# Esquema_V3.net
KiCad netlist of a schematic drawn in Altium Designer
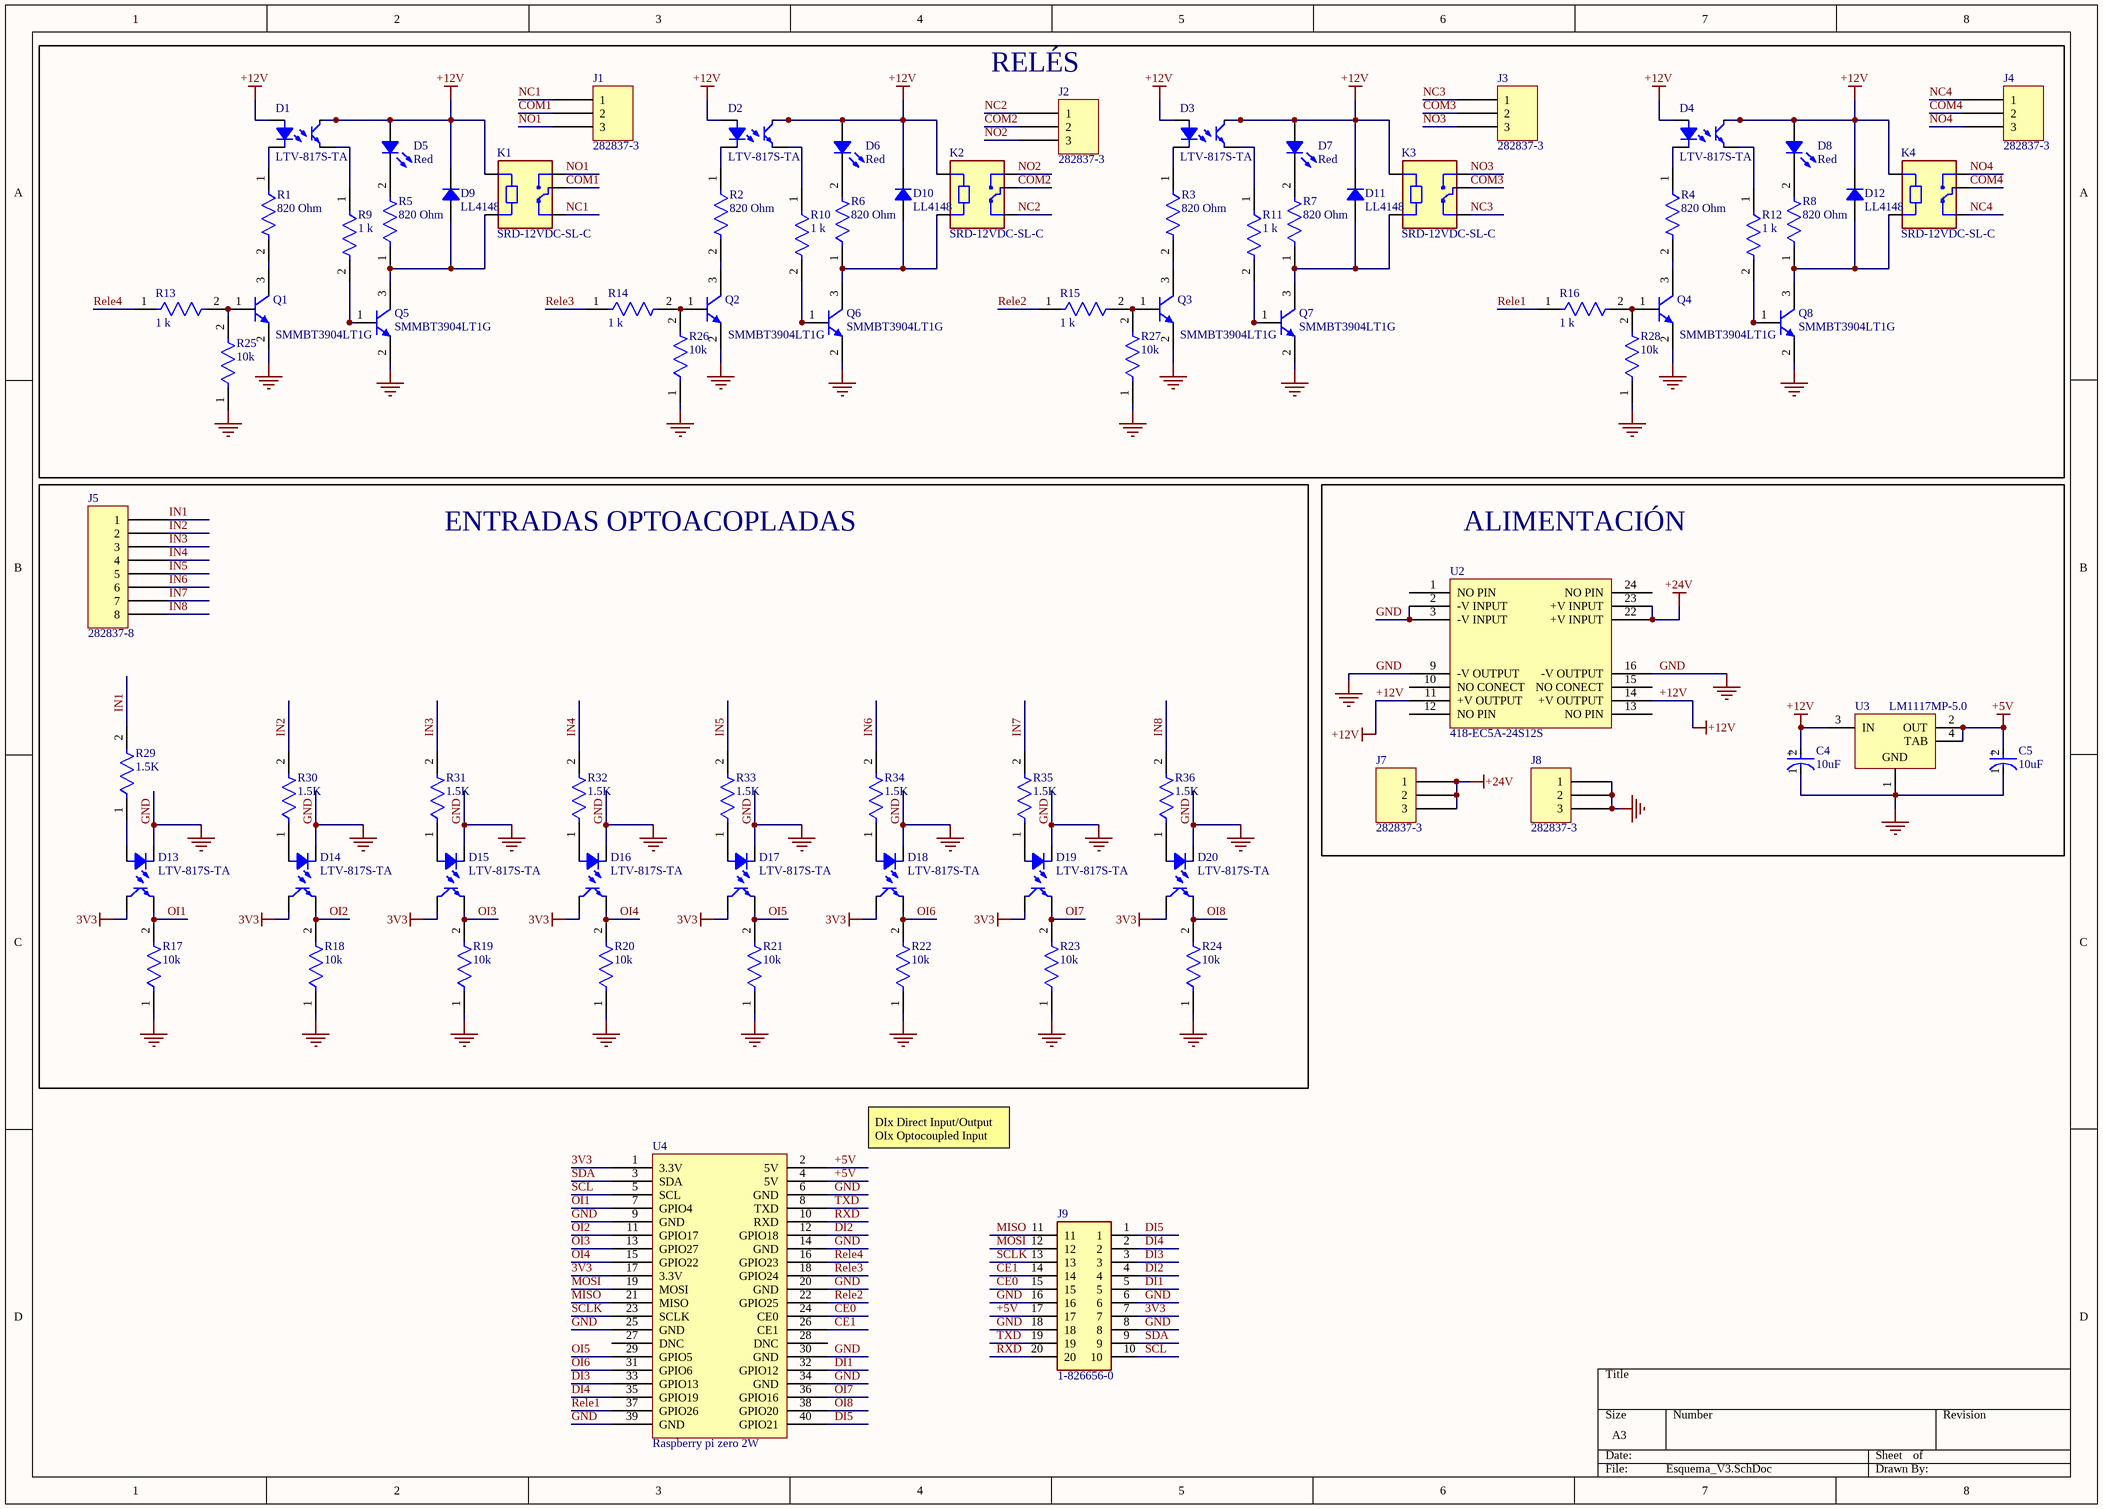
[diagram p0: Esquema_V3.SchDoc]

(export (version "E")
  (design (tool "Eeschema 10.0.6"))
  (components
    (comp (ref "C4")
      (value "10uF")
      (footprint "FP-TAJA-MFG")
      (description "TAJA106M010RNJ 10uF 10V  ±20% 3Ω 1206  SMD Tantalum Capacitor")
      (fields (field (name "TOLERANCE") "20%") (field (name "VOLTAGE") "10V"))
      (libsource (lib "Altium Content Vault") (part "203bc49f2ac43e59fd269a8c329ed05"))
    )
    (comp (ref "C5")
      (value "10uF")
      (footprint "FP-TAJA-MFG")
      (description "TAJA106M010RNJ 10uF 10V  ±20% 3Ω 1206  SMD Tantalum Capacitor")
      (fields (field (name "TOLERANCE") "20%") (field (name "VOLTAGE") "10V"))
      (libsource (lib "Altium Content Vault") (part "203bc49f2ac43e59fd269a8c329ed05"))
    )
    (comp (ref "D1")
      (value "LTV-817S-TA")
      (footprint "LITEON LTV-817")
      (description "OPTOISOLATR 5KV TRANSISTOR 4-SMD")
      (fields (field (name "MANUFACTURER") "Lite-On Inc."))
      (libsource (lib "Celestial Altium Library - altium_library") (part "Optoisolator"))
    )
    (comp (ref "D2")
      (value "LTV-817S-TA")
      (footprint "LITEON LTV-817")
      (description "OPTOISOLATR 5KV TRANSISTOR 4-SMD")
      (fields (field (name "MANUFACTURER") "Lite-On Inc."))
      (libsource (lib "Celestial Altium Library - altium_library") (part "Optoisolator"))
    )
    (comp (ref "D3")
      (value "LTV-817S-TA")
      (footprint "LITEON LTV-817")
      (description "OPTOISOLATR 5KV TRANSISTOR 4-SMD")
      (fields (field (name "MANUFACTURER") "Lite-On Inc."))
      (libsource (lib "Celestial Altium Library - altium_library") (part "Optoisolator"))
    )
    (comp (ref "D4")
      (value "LTV-817S-TA")
      (footprint "LITEON LTV-817")
      (description "OPTOISOLATR 5KV TRANSISTOR 4-SMD")
      (fields (field (name "MANUFACTURER") "Lite-On Inc."))
      (libsource (lib "Celestial Altium Library - altium_library") (part "Optoisolator"))
    )
    (comp (ref "D5")
      (value "Red")
      (footprint "LED 1206_3216 RED")
      (description "LED RED CLEAR SMD")
      (fields (field (name "PART NUMBER") "LTST-C150KAKT") (field (name "MANUFACTURER") "Lite-On Inc."))
      (libsource (lib "Celestial Altium Library - altium_library") (part "LED"))
    )
    (comp (ref "D6")
      (value "Red")
      (footprint "LED 1206_3216 RED")
      (description "LED RED CLEAR SMD")
      (fields (field (name "PART NUMBER") "LTST-C150KAKT") (field (name "MANUFACTURER") "Lite-On Inc."))
      (libsource (lib "Celestial Altium Library - altium_library") (part "LED"))
    )
    (comp (ref "D7")
      (value "Red")
      (footprint "LED 1206_3216 RED")
      (description "LED RED CLEAR SMD")
      (fields (field (name "PART NUMBER") "LTST-C150KAKT") (field (name "MANUFACTURER") "Lite-On Inc."))
      (libsource (lib "Celestial Altium Library - altium_library") (part "LED"))
    )
    (comp (ref "D8")
      (value "Red")
      (footprint "LED 1206_3216 RED")
      (description "LED RED CLEAR SMD")
      (fields (field (name "PART NUMBER") "LTST-C150KAKT") (field (name "MANUFACTURER") "Lite-On Inc."))
      (libsource (lib "Celestial Altium Library - altium_library") (part "LED"))
    )
    (comp (ref "D9")
      (value "LL4148")
      (footprint "SOD-80 MiniMELF")
      (description "DIODE GEN PURP 100V 200MA SOD80")
      (fields (field (name "MANUFACTURER") "ON Semiconductor"))
      (libsource (lib "Celestial Altium Library - altium_library") (part "Diode"))
    )
    (comp (ref "D10")
      (value "LL4148")
      (footprint "SOD-80 MiniMELF")
      (description "DIODE GEN PURP 100V 200MA SOD80")
      (fields (field (name "MANUFACTURER") "ON Semiconductor"))
      (libsource (lib "Celestial Altium Library - altium_library") (part "Diode"))
    )
    (comp (ref "D11")
      (value "LL4148")
      (footprint "SOD-80 MiniMELF")
      (description "DIODE GEN PURP 100V 200MA SOD80")
      (fields (field (name "MANUFACTURER") "ON Semiconductor"))
      (libsource (lib "Celestial Altium Library - altium_library") (part "Diode"))
    )
    (comp (ref "D12")
      (value "LL4148")
      (footprint "SOD-80 MiniMELF")
      (description "DIODE GEN PURP 100V 200MA SOD80")
      (fields (field (name "MANUFACTURER") "ON Semiconductor"))
      (libsource (lib "Celestial Altium Library - altium_library") (part "Diode"))
    )
    (comp (ref "D13")
      (value "LTV-817S-TA")
      (footprint "LITEON LTV-817")
      (description "OPTOISOLATR 5KV TRANSISTOR 4-SMD")
      (fields (field (name "MANUFACTURER") "Lite-On Inc."))
      (libsource (lib "Celestial Altium Library - altium_library") (part "Optoisolator"))
    )
    (comp (ref "D14")
      (value "LTV-817S-TA")
      (footprint "LITEON LTV-817")
      (description "OPTOISOLATR 5KV TRANSISTOR 4-SMD")
      (fields (field (name "MANUFACTURER") "Lite-On Inc."))
      (libsource (lib "Celestial Altium Library - altium_library") (part "Optoisolator"))
    )
    (comp (ref "D15")
      (value "LTV-817S-TA")
      (footprint "LITEON LTV-817")
      (description "OPTOISOLATR 5KV TRANSISTOR 4-SMD")
      (fields (field (name "MANUFACTURER") "Lite-On Inc."))
      (libsource (lib "Celestial Altium Library - altium_library") (part "Optoisolator"))
    )
    (comp (ref "D16")
      (value "LTV-817S-TA")
      (footprint "LITEON LTV-817")
      (description "OPTOISOLATR 5KV TRANSISTOR 4-SMD")
      (fields (field (name "MANUFACTURER") "Lite-On Inc."))
      (libsource (lib "Celestial Altium Library - altium_library") (part "Optoisolator"))
    )
    (comp (ref "D17")
      (value "LTV-817S-TA")
      (footprint "LITEON LTV-817")
      (description "OPTOISOLATR 5KV TRANSISTOR 4-SMD")
      (fields (field (name "MANUFACTURER") "Lite-On Inc."))
      (libsource (lib "Celestial Altium Library - altium_library") (part "Optoisolator"))
    )
    (comp (ref "D18")
      (value "LTV-817S-TA")
      (footprint "LITEON LTV-817")
      (description "OPTOISOLATR 5KV TRANSISTOR 4-SMD")
      (fields (field (name "MANUFACTURER") "Lite-On Inc."))
      (libsource (lib "Celestial Altium Library - altium_library") (part "Optoisolator"))
    )
    (comp (ref "D19")
      (value "LTV-817S-TA")
      (footprint "LITEON LTV-817")
      (description "OPTOISOLATR 5KV TRANSISTOR 4-SMD")
      (fields (field (name "MANUFACTURER") "Lite-On Inc."))
      (libsource (lib "Celestial Altium Library - altium_library") (part "Optoisolator"))
    )
    (comp (ref "D20")
      (value "LTV-817S-TA")
      (footprint "LITEON LTV-817")
      (description "OPTOISOLATR 5KV TRANSISTOR 4-SMD")
      (fields (field (name "MANUFACTURER") "Lite-On Inc."))
      (libsource (lib "Celestial Altium Library - altium_library") (part "Optoisolator"))
    )
    (comp (ref "J1")
      (value "282837-3")
      (footprint "TE 282837-3")
      (description "TERM BLK 3P SIDE ENT 5.08MM PCB")
      (fields (field (name "MANUFACTURER") "TE Connectivity AMP Connectors") (field (name "VOLTAGE") "300 V"))
      (libsource (lib "") (part "3 Pin_1"))
    )
    (comp (ref "J2")
      (value "282837-3")
      (footprint "TE 282837-3")
      (description "TERM BLK 3P SIDE ENT 5.08MM PCB")
      (fields (field (name "MANUFACTURER") "TE Connectivity AMP Connectors") (field (name "VOLTAGE") "300 V"))
      (libsource (lib "") (part "3 Pin_1"))
    )
    (comp (ref "J3")
      (value "282837-3")
      (footprint "TE 282837-3")
      (description "TERM BLK 3P SIDE ENT 5.08MM PCB")
      (fields (field (name "MANUFACTURER") "TE Connectivity AMP Connectors") (field (name "VOLTAGE") "300 V"))
      (libsource (lib "") (part "3 Pin_1"))
    )
    (comp (ref "J4")
      (value "282837-3")
      (footprint "TE 282837-3")
      (description "TERM BLK 3P SIDE ENT 5.08MM PCB")
      (fields (field (name "MANUFACTURER") "TE Connectivity AMP Connectors") (field (name "VOLTAGE") "300 V"))
      (libsource (lib "") (part "3 Pin_1"))
    )
    (comp (ref "J5")
      (value "282837-8")
      (footprint "TE 282837-8")
      (description "TERM BLK 8P SIDE ENT 5.08MM PCB")
      (fields (field (name "MANUFACTURER") "TE Connectivity AMP Connectors") (field (name "VOLTAGE") "300 V"))
      (libsource (lib "Celestial Altium Library - altium_library") (part "8 Pin"))
    )
    (comp (ref "J7")
      (value "282837-3")
      (footprint "TE 282837-3")
      (description "TERM BLK 3P SIDE ENT 5.08MM PCB")
      (fields (field (name "MANUFACTURER") "TE Connectivity AMP Connectors") (field (name "VOLTAGE") "300 V"))
      (libsource (lib "Celestial Altium Library - altium_library") (part "3 Pin"))
    )
    (comp (ref "J8")
      (value "282837-3")
      (footprint "TE 282837-3")
      (description "TERM BLK 3P SIDE ENT 5.08MM PCB")
      (fields (field (name "MANUFACTURER") "TE Connectivity AMP Connectors") (field (name "VOLTAGE") "300 V"))
      (libsource (lib "Celestial Altium Library - altium_library") (part "3 Pin"))
    )
    (comp (ref "J9")
      (value "1-826656-0")
      (footprint "TE_1-826656-0")
      (description "Conn Unshrouded Header HDR 20 POS 2.54mm Solder ST Thru-Hole Box")
      (fields (field (name "MF") "TE Connectivity"))
      (libsource (lib "1-826656-0") (part "1-826656-0"))
    )
    (comp (ref "K1")
      (value "SRD-12VDC-SL-C")
      (footprint "RELAY_SRD-05VDC-SL-C")
      (fields (field (name "MF") "Songle Relay") (field (name "MP") "SRD-05VDC-SL-C"))
      (libsource (lib "SRD-05VDC-SL-C") (part "SRD-05VDC-SL-C"))
    )
    (comp (ref "K2")
      (value "SRD-12VDC-SL-C")
      (footprint "RELAY_SRD-05VDC-SL-C")
      (fields (field (name "MF") "Songle Relay") (field (name "MP") "SRD-05VDC-SL-C"))
      (libsource (lib "SRD-05VDC-SL-C") (part "SRD-05VDC-SL-C"))
    )
    (comp (ref "K3")
      (value "SRD-12VDC-SL-C")
      (footprint "RELAY_SRD-05VDC-SL-C")
      (fields (field (name "MF") "Songle Relay") (field (name "MP") "SRD-05VDC-SL-C"))
      (libsource (lib "SRD-05VDC-SL-C") (part "SRD-05VDC-SL-C"))
    )
    (comp (ref "K4")
      (value "SRD-12VDC-SL-C")
      (footprint "RELAY_SRD-05VDC-SL-C")
      (fields (field (name "MF") "Songle Relay") (field (name "MP") "SRD-05VDC-SL-C"))
      (libsource (lib "SRD-05VDC-SL-C") (part "SRD-05VDC-SL-C"))
    )
    (comp (ref "Q1")
      (value "SMMBT3904LT1G")
      (footprint "ONSC-SOT-23-3-318-08_V")
      (description "General Purpose Transistor, NPN Silicon, 3-Pin SOT-23, Pb-Free, Tape and Reel")
      (fields (field (name "MANUFACTURER") "On Semiconductor"))
      (libsource (lib "Altium Content Vault") (part "ONSC-NPN-B1E2C3-3"))
    )
    (comp (ref "Q2")
      (value "SMMBT3904LT1G")
      (footprint "ONSC-SOT-23-3-318-08_V")
      (description "General Purpose Transistor, NPN Silicon, 3-Pin SOT-23, Pb-Free, Tape and Reel")
      (fields (field (name "MANUFACTURER") "On Semiconductor"))
      (libsource (lib "Altium Content Vault") (part "ONSC-NPN-B1E2C3-3"))
    )
    (comp (ref "Q3")
      (value "SMMBT3904LT1G")
      (footprint "ONSC-SOT-23-3-318-08_V")
      (description "General Purpose Transistor, NPN Silicon, 3-Pin SOT-23, Pb-Free, Tape and Reel")
      (fields (field (name "MANUFACTURER") "On Semiconductor"))
      (libsource (lib "Altium Content Vault") (part "ONSC-NPN-B1E2C3-3"))
    )
    (comp (ref "Q4")
      (value "SMMBT3904LT1G")
      (footprint "ONSC-SOT-23-3-318-08_V")
      (description "General Purpose Transistor, NPN Silicon, 3-Pin SOT-23, Pb-Free, Tape and Reel")
      (fields (field (name "MANUFACTURER") "On Semiconductor"))
      (libsource (lib "Altium Content Vault") (part "ONSC-NPN-B1E2C3-3"))
    )
    (comp (ref "Q5")
      (value "SMMBT3904LT1G")
      (footprint "ONSC-SOT-23-3-318-08_V")
      (description "General Purpose Transistor, NPN Silicon, 3-Pin SOT-23, Pb-Free, Tape and Reel")
      (fields (field (name "MANUFACTURER") "On Semiconductor"))
      (libsource (lib "Altium Content Vault") (part "ONSC-NPN-B1E2C3-3"))
    )
    (comp (ref "Q6")
      (value "SMMBT3904LT1G")
      (footprint "ONSC-SOT-23-3-318-08_V")
      (description "General Purpose Transistor, NPN Silicon, 3-Pin SOT-23, Pb-Free, Tape and Reel")
      (fields (field (name "MANUFACTURER") "On Semiconductor"))
      (libsource (lib "Altium Content Vault") (part "ONSC-NPN-B1E2C3-3"))
    )
    (comp (ref "Q7")
      (value "SMMBT3904LT1G")
      (footprint "ONSC-SOT-23-3-318-08_V")
      (description "General Purpose Transistor, NPN Silicon, 3-Pin SOT-23, Pb-Free, Tape and Reel")
      (fields (field (name "MANUFACTURER") "On Semiconductor"))
      (libsource (lib "Altium Content Vault") (part "ONSC-NPN-B1E2C3-3"))
    )
    (comp (ref "Q8")
      (value "SMMBT3904LT1G")
      (footprint "ONSC-SOT-23-3-318-08_V")
      (description "General Purpose Transistor, NPN Silicon, 3-Pin SOT-23, Pb-Free, Tape and Reel")
      (fields (field (name "MANUFACTURER") "On Semiconductor"))
      (libsource (lib "Altium Content Vault") (part "ONSC-NPN-B1E2C3-3"))
    )
    (comp (ref "R1")
      (value "820 Ohm")
      (footprint "FP-CRCW0603-HPe3-MFG")
      (description "RES Thick Film, 820Ω, 1%, 0.33W, 100ppm/°C, 0603")
      (fields (field (name "TOLERANCE") "1%"))
      (libsource (lib "Altium Content Vault") (part "1029c3af85768c4190bb7ad29bc67b5"))
    )
    (comp (ref "R2")
      (value "820 Ohm")
      (footprint "FP-CRCW0603-HPe3-MFG")
      (description "RES Thick Film, 820Ω, 1%, 0.33W, 100ppm/°C, 0603")
      (fields (field (name "TOLERANCE") "1%"))
      (libsource (lib "Altium Content Vault") (part "1029c3af85768c4190bb7ad29bc67b5"))
    )
    (comp (ref "R3")
      (value "820 Ohm")
      (footprint "FP-CRCW0603-HPe3-MFG")
      (description "RES Thick Film, 820Ω, 1%, 0.33W, 100ppm/°C, 0603")
      (fields (field (name "TOLERANCE") "1%"))
      (libsource (lib "Altium Content Vault") (part "1029c3af85768c4190bb7ad29bc67b5"))
    )
    (comp (ref "R4")
      (value "820 Ohm")
      (footprint "FP-CRCW0603-HPe3-MFG")
      (description "RES Thick Film, 820Ω, 1%, 0.33W, 100ppm/°C, 0603")
      (fields (field (name "TOLERANCE") "1%"))
      (libsource (lib "Altium Content Vault") (part "1029c3af85768c4190bb7ad29bc67b5"))
    )
    (comp (ref "R5")
      (value "820 Ohm")
      (footprint "FP-CRCW0603-HPe3-MFG")
      (description "RES Thick Film, 820Ω, 1%, 0.33W, 100ppm/°C, 0603")
      (fields (field (name "TOLERANCE") "1%"))
      (libsource (lib "Altium Content Vault") (part "1029c3af85768c4190bb7ad29bc67b5"))
    )
    (comp (ref "R6")
      (value "820 Ohm")
      (footprint "FP-CRCW0603-HPe3-MFG")
      (description "RES Thick Film, 820Ω, 1%, 0.33W, 100ppm/°C, 0603")
      (fields (field (name "TOLERANCE") "1%"))
      (libsource (lib "Altium Content Vault") (part "1029c3af85768c4190bb7ad29bc67b5"))
    )
    (comp (ref "R7")
      (value "820 Ohm")
      (footprint "FP-CRCW0603-HPe3-MFG")
      (description "RES Thick Film, 820Ω, 1%, 0.33W, 100ppm/°C, 0603")
      (fields (field (name "TOLERANCE") "1%"))
      (libsource (lib "Altium Content Vault") (part "1029c3af85768c4190bb7ad29bc67b5"))
    )
    (comp (ref "R8")
      (value "820 Ohm")
      (footprint "FP-CRCW0603-HPe3-MFG")
      (description "RES Thick Film, 820Ω, 1%, 0.33W, 100ppm/°C, 0603")
      (fields (field (name "TOLERANCE") "1%"))
      (libsource (lib "Altium Content Vault") (part "1029c3af85768c4190bb7ad29bc67b5"))
    )
    (comp (ref "R9")
      (value "1 k")
      (footprint "FP-MCT0603-IPC_C")
      (description "MCT0603PD1001DP500 RES SMD 100 OHM 1% 1/8W 0603")
      (fields (field (name "TOLERANCE") "0.5%"))
      (libsource (lib "Altium Content Vault") (part "1029c3af85768c4190bb7ad29bc67b5"))
    )
    (comp (ref "R10")
      (value "1 k")
      (footprint "FP-MCT0603-IPC_C")
      (description "MCT0603PD1001DP500 RES SMD 100 OHM 1% 1/8W 0603")
      (fields (field (name "TOLERANCE") "0.5%"))
      (libsource (lib "Altium Content Vault") (part "1029c3af85768c4190bb7ad29bc67b5"))
    )
    (comp (ref "R11")
      (value "1 k")
      (footprint "FP-MCT0603-IPC_C")
      (description "MCT0603PD1001DP500 RES SMD 100 OHM 1% 1/8W 0603")
      (fields (field (name "TOLERANCE") "0.5%"))
      (libsource (lib "Altium Content Vault") (part "1029c3af85768c4190bb7ad29bc67b5"))
    )
    (comp (ref "R12")
      (value "1 k")
      (footprint "FP-MCT0603-IPC_C")
      (description "MCT0603PD1001DP500 RES SMD 100 OHM 1% 1/8W 0603")
      (fields (field (name "TOLERANCE") "0.5%"))
      (libsource (lib "Altium Content Vault") (part "1029c3af85768c4190bb7ad29bc67b5"))
    )
    (comp (ref "R13")
      (value "1 k")
      (footprint "FP-MCT0603-IPC_C")
      (description "MCT0603PD1001DP500 RES SMD 100 OHM 1% 1/8W 0603")
      (fields (field (name "TOLERANCE") "0.5%"))
      (libsource (lib "Altium Content Vault") (part "1029c3af85768c4190bb7ad29bc67b5"))
    )
    (comp (ref "R14")
      (value "1 k")
      (footprint "FP-MCT0603-IPC_C")
      (description "MCT0603PD1001DP500 RES SMD 100 OHM 1% 1/8W 0603")
      (fields (field (name "TOLERANCE") "0.5%"))
      (libsource (lib "Altium Content Vault") (part "1029c3af85768c4190bb7ad29bc67b5"))
    )
    (comp (ref "R15")
      (value "1 k")
      (footprint "FP-MCT0603-IPC_C")
      (description "MCT0603PD1001DP500 RES SMD 100 OHM 1% 1/8W 0603")
      (fields (field (name "TOLERANCE") "0.5%"))
      (libsource (lib "Altium Content Vault") (part "1029c3af85768c4190bb7ad29bc67b5"))
    )
    (comp (ref "R16")
      (value "1 k")
      (footprint "FP-MCT0603-IPC_C")
      (description "MCT0603PD1001DP500 RES SMD 100 OHM 1% 1/8W 0603")
      (fields (field (name "TOLERANCE") "0.5%"))
      (libsource (lib "Altium Content Vault") (part "1029c3af85768c4190bb7ad29bc67b5"))
    )
    (comp (ref "R17")
      (value "10k")
      (footprint "FP-MCT0603-IPC_B")
      (description "MCT0603MD1002BP100 RES SMD 10k OHM 1% 1/8W 0603")
      (fields (field (name "TOLERANCE") "0.1%"))
      (libsource (lib "Altium Content Vault") (part "1029c3af85768c4190bb7ad29bc67b5"))
    )
    (comp (ref "R18")
      (value "10k")
      (footprint "FP-MCT0603-IPC_B")
      (description "MCT0603MD1002BP100 RES SMD 10k OHM 1% 1/8W 0603")
      (fields (field (name "TOLERANCE") "0.1%"))
      (libsource (lib "Altium Content Vault") (part "1029c3af85768c4190bb7ad29bc67b5"))
    )
    (comp (ref "R19")
      (value "10k")
      (footprint "FP-MCT0603-IPC_B")
      (description "MCT0603MD1002BP100 RES SMD 10k OHM 1% 1/8W 0603")
      (fields (field (name "TOLERANCE") "0.1%"))
      (libsource (lib "Altium Content Vault") (part "1029c3af85768c4190bb7ad29bc67b5"))
    )
    (comp (ref "R20")
      (value "10k")
      (footprint "FP-MCT0603-IPC_B")
      (description "MCT0603MD1002BP100 RES SMD 10k OHM 1% 1/8W 0603")
      (fields (field (name "TOLERANCE") "0.1%"))
      (libsource (lib "Altium Content Vault") (part "1029c3af85768c4190bb7ad29bc67b5"))
    )
    (comp (ref "R21")
      (value "10k")
      (footprint "FP-MCT0603-IPC_B")
      (description "MCT0603MD1002BP100 RES SMD 10k OHM 1% 1/8W 0603")
      (fields (field (name "TOLERANCE") "0.1%"))
      (libsource (lib "Altium Content Vault") (part "1029c3af85768c4190bb7ad29bc67b5"))
    )
    (comp (ref "R22")
      (value "10k")
      (footprint "FP-MCT0603-IPC_B")
      (description "MCT0603MD1002BP100 RES SMD 10k OHM 1% 1/8W 0603")
      (fields (field (name "TOLERANCE") "0.1%"))
      (libsource (lib "Altium Content Vault") (part "1029c3af85768c4190bb7ad29bc67b5"))
    )
    (comp (ref "R23")
      (value "10k")
      (footprint "FP-MCT0603-IPC_B")
      (description "MCT0603MD1002BP100 RES SMD 10k OHM 1% 1/8W 0603")
      (fields (field (name "TOLERANCE") "0.1%"))
      (libsource (lib "Altium Content Vault") (part "1029c3af85768c4190bb7ad29bc67b5"))
    )
    (comp (ref "R24")
      (value "10k")
      (footprint "FP-MCT0603-IPC_B")
      (description "MCT0603MD1002BP100 RES SMD 10k OHM 1% 1/8W 0603")
      (fields (field (name "TOLERANCE") "0.1%"))
      (libsource (lib "Altium Content Vault") (part "1029c3af85768c4190bb7ad29bc67b5"))
    )
    (comp (ref "R25")
      (value "10k")
      (footprint "FP-MCT0603-IPC_B")
      (description "MCT0603MD1002BP100 RES SMD 10k OHM 1% 1/8W 0603")
      (fields (field (name "TOLERANCE") "0.1%"))
      (libsource (lib "Altium Content Vault") (part "1029c3af85768c4190bb7ad29bc67b5"))
    )
    (comp (ref "R26")
      (value "10k")
      (footprint "FP-MCT0603-IPC_B")
      (description "MCT0603MD1002BP100 RES SMD 10k OHM 1% 1/8W 0603")
      (fields (field (name "TOLERANCE") "0.1%"))
      (libsource (lib "Altium Content Vault") (part "1029c3af85768c4190bb7ad29bc67b5"))
    )
    (comp (ref "R27")
      (value "10k")
      (footprint "FP-MCT0603-IPC_B")
      (description "MCT0603MD1002BP100 RES SMD 10k OHM 1% 1/8W 0603")
      (fields (field (name "TOLERANCE") "0.1%"))
      (libsource (lib "Altium Content Vault") (part "1029c3af85768c4190bb7ad29bc67b5"))
    )
    (comp (ref "R28")
      (value "10k")
      (footprint "FP-MCT0603-IPC_B")
      (description "MCT0603MD1002BP100 RES SMD 10k OHM 1% 1/8W 0603")
      (fields (field (name "TOLERANCE") "0.1%"))
      (libsource (lib "Altium Content Vault") (part "1029c3af85768c4190bb7ad29bc67b5"))
    )
    (comp (ref "R29")
      (value "1.5K")
      (footprint "FP-CRCW0603-e3-IPC_C")
      (description "CRCW06031K50FKEC RES Thick Film, 1.5kΩ, 1%, 0.1W, 100ppm/°C, 0603")
      (fields (field (name "TOLERANCE") "1%"))
      (libsource (lib "Altium Content Vault") (part "1029c3af85768c4190bb7ad29bc67b5"))
    )
    (comp (ref "R30")
      (value "1.5K")
      (footprint "FP-CRCW0603-e3-IPC_C")
      (description "CRCW06031K50FKEC RES Thick Film, 1.5kΩ, 1%, 0.1W, 100ppm/°C, 0603")
      (fields (field (name "TOLERANCE") "1%"))
      (libsource (lib "Altium Content Vault") (part "1029c3af85768c4190bb7ad29bc67b5"))
    )
    (comp (ref "R31")
      (value "1.5K")
      (footprint "FP-CRCW0603-e3-IPC_C")
      (description "CRCW06031K50FKEC RES Thick Film, 1.5kΩ, 1%, 0.1W, 100ppm/°C, 0603")
      (fields (field (name "TOLERANCE") "1%"))
      (libsource (lib "Altium Content Vault") (part "1029c3af85768c4190bb7ad29bc67b5"))
    )
    (comp (ref "R32")
      (value "1.5K")
      (footprint "FP-CRCW0603-e3-IPC_C")
      (description "CRCW06031K50FKEC RES Thick Film, 1.5kΩ, 1%, 0.1W, 100ppm/°C, 0603")
      (fields (field (name "TOLERANCE") "1%"))
      (libsource (lib "Altium Content Vault") (part "1029c3af85768c4190bb7ad29bc67b5"))
    )
    (comp (ref "R33")
      (value "1.5K")
      (footprint "FP-CRCW0603-e3-IPC_C")
      (description "CRCW06031K50FKEC RES Thick Film, 1.5kΩ, 1%, 0.1W, 100ppm/°C, 0603")
      (fields (field (name "TOLERANCE") "1%"))
      (libsource (lib "Altium Content Vault") (part "1029c3af85768c4190bb7ad29bc67b5"))
    )
    (comp (ref "R34")
      (value "1.5K")
      (footprint "FP-CRCW0603-e3-IPC_C")
      (description "CRCW06031K50FKEC RES Thick Film, 1.5kΩ, 1%, 0.1W, 100ppm/°C, 0603")
      (fields (field (name "TOLERANCE") "1%"))
      (libsource (lib "Altium Content Vault") (part "1029c3af85768c4190bb7ad29bc67b5"))
    )
    (comp (ref "R35")
      (value "1.5K")
      (footprint "FP-CRCW0603-e3-IPC_C")
      (description "CRCW06031K50FKEC RES Thick Film, 1.5kΩ, 1%, 0.1W, 100ppm/°C, 0603")
      (fields (field (name "TOLERANCE") "1%"))
      (libsource (lib "Altium Content Vault") (part "1029c3af85768c4190bb7ad29bc67b5"))
    )
    (comp (ref "R36")
      (value "1.5K")
      (footprint "FP-CRCW0603-e3-IPC_C")
      (description "CRCW06031K50FKEC RES Thick Film, 1.5kΩ, 1%, 0.1W, 100ppm/°C, 0603")
      (fields (field (name "TOLERANCE") "1%"))
      (libsource (lib "Altium Content Vault") (part "1029c3af85768c4190bb7ad29bc67b5"))
    )
    (comp (ref "U2")
      (value "418-EC5A-24S12S")
      (footprint "418-EC5A-24S12S")
      (libsource (lib "Raspberry") (part "418-EC5A-24S12S"))
    )
    (comp (ref "U3")
      (value "LM1117MP-5.0")
      (footprint "MP04A_N")
      (description "800mA Low-Dropout Linear Regulator, 4-pin SOT-223")
      (fields (field (name "MANUFACTURER") "National Semiconductor"))
      (libsource (lib "Altium Content Vault") (part "PM-REG-LM1086-SOT4"))
    )
    (comp (ref "U4")
      (value "Raspberry pi zero 2W")
      (footprint "PCBComponent_1")
      (libsource (lib "Raspberry") (part "Raspberry pi zero 2W"))
    )
  )
  (nets
    (net (code "1") (name "+5V") (class "Default")
      (node (ref "C5") (pin "2") (pinfunction "A_2") (pintype "passive"))
      (node (ref "J9") (pin "17") (pinfunction "17_17") (pintype "passive"))
      (node (ref "U3") (pin "2") (pinfunction "OUT_2") (pintype "power_in"))
      (node (ref "U3") (pin "4") (pinfunction "TAB_4") (pintype "power_in"))
      (node (ref "U4") (pin "2") (pinfunction "5V_2") (pintype "passive"))
      (node (ref "U4") (pin "4") (pinfunction "5V_4") (pintype "passive"))
    )
    (net (code "2") (name "+12V") (class "Default")
      (node (ref "C4") (pin "2") (pinfunction "A_2") (pintype "passive"))
      (node (ref "D1") (pin "1") (pinfunction "1_1") (pintype "passive"))
      (node (ref "D1") (pin "4") (pinfunction "4_4") (pintype "passive"))
      (node (ref "D10") (pin "2") (pinfunction "2_2") (pintype "passive"))
      (node (ref "D11") (pin "2") (pinfunction "2_2") (pintype "passive"))
      (node (ref "D12") (pin "2") (pinfunction "2_2") (pintype "passive"))
      (node (ref "D2") (pin "1") (pinfunction "1_1") (pintype "passive"))
      (node (ref "D2") (pin "4") (pinfunction "4_4") (pintype "passive"))
      (node (ref "D3") (pin "1") (pinfunction "1_1") (pintype "passive"))
      (node (ref "D3") (pin "4") (pinfunction "4_4") (pintype "passive"))
      (node (ref "D4") (pin "1") (pinfunction "1_1") (pintype "passive"))
      (node (ref "D4") (pin "4") (pinfunction "4_4") (pintype "passive"))
      (node (ref "D5") (pin "1") (pinfunction "1_1") (pintype "passive"))
      (node (ref "D6") (pin "1") (pinfunction "1_1") (pintype "passive"))
      (node (ref "D7") (pin "1") (pinfunction "1_1") (pintype "passive"))
      (node (ref "D8") (pin "1") (pinfunction "1_1") (pintype "passive"))
      (node (ref "D9") (pin "2") (pinfunction "2_2") (pintype "passive"))
      (node (ref "K1") (pin "A1") (pinfunction "A1_A1") (pintype "passive"))
      (node (ref "K2") (pin "A1") (pinfunction "A1_A1") (pintype "passive"))
      (node (ref "K3") (pin "A1") (pinfunction "A1_A1") (pintype "passive"))
      (node (ref "K4") (pin "A1") (pinfunction "A1_A1") (pintype "passive"))
      (node (ref "U2") (pin "11") (pinfunction "+V_OUTPUT_11") (pintype "passive"))
      (node (ref "U2") (pin "14") (pinfunction "+V_OUTPUT_14") (pintype "passive"))
      (node (ref "U3") (pin "3") (pinfunction "IN_3") (pintype "power_in"))
    )
    (net (code "3") (name "+24V") (class "Default")
      (node (ref "J7") (pin "1") (pinfunction "1_1") (pintype "passive"))
      (node (ref "J7") (pin "2") (pinfunction "2_2") (pintype "passive"))
      (node (ref "J7") (pin "3") (pinfunction "3_3") (pintype "passive"))
      (node (ref "U2") (pin "22") (pinfunction "+V_INPUT_22") (pintype "passive"))
      (node (ref "U2") (pin "23") (pinfunction "+V_INPUT_23") (pintype "passive"))
    )
    (net (code "4") (name "/CE0") (class "Default")
      (node (ref "J9") (pin "15") (pinfunction "15_15") (pintype "passive"))
      (node (ref "U4") (pin "24") (pinfunction "CE0_24") (pintype "passive"))
    )
    (net (code "5") (name "/CE1") (class "Default")
      (node (ref "J9") (pin "14") (pinfunction "14_14") (pintype "passive"))
      (node (ref "U4") (pin "26") (pinfunction "CE1_26") (pintype "passive"))
    )
    (net (code "6") (name "/COM1") (class "Default")
      (node (ref "J1") (pin "2") (pinfunction "2_2") (pintype "passive"))
      (node (ref "K1") (pin "COM") (pinfunction "COM_COM") (pintype "passive"))
    )
    (net (code "7") (name "/COM2") (class "Default")
      (node (ref "J2") (pin "2") (pinfunction "2_2") (pintype "passive"))
      (node (ref "K2") (pin "COM") (pinfunction "COM_COM") (pintype "passive"))
    )
    (net (code "8") (name "/COM3") (class "Default")
      (node (ref "J3") (pin "2") (pinfunction "2_2") (pintype "passive"))
      (node (ref "K3") (pin "COM") (pinfunction "COM_COM") (pintype "passive"))
    )
    (net (code "9") (name "/COM4") (class "Default")
      (node (ref "J4") (pin "2") (pinfunction "2_2") (pintype "passive"))
      (node (ref "K4") (pin "COM") (pinfunction "COM_COM") (pintype "passive"))
    )
    (net (code "10") (name "/DI1") (class "Default")
      (node (ref "J9") (pin "5") (pinfunction "5_5") (pintype "passive"))
      (node (ref "U4") (pin "32") (pinfunction "GPIO12_32") (pintype "passive"))
    )
    (net (code "11") (name "/DI2") (class "Default")
      (node (ref "J9") (pin "4") (pinfunction "4_4") (pintype "passive"))
      (node (ref "U4") (pin "12") (pinfunction "GPIO18_12") (pintype "passive"))
    )
    (net (code "12") (name "/DI3") (class "Default")
      (node (ref "J9") (pin "3") (pinfunction "3_3") (pintype "passive"))
      (node (ref "U4") (pin "33") (pinfunction "GPIO13_33") (pintype "passive"))
    )
    (net (code "13") (name "/DI4") (class "Default")
      (node (ref "J9") (pin "2") (pinfunction "2_2") (pintype "passive"))
      (node (ref "U4") (pin "35") (pinfunction "GPIO19_35") (pintype "passive"))
    )
    (net (code "14") (name "/DI5") (class "Default")
      (node (ref "J9") (pin "1") (pinfunction "1_1") (pintype "passive"))
      (node (ref "U4") (pin "40") (pinfunction "GPIO21_40") (pintype "passive"))
    )
    (net (code "15") (name "/IN1") (class "Default")
      (node (ref "J5") (pin "1") (pinfunction "1_1") (pintype "passive"))
      (node (ref "R29") (pin "2") (pinfunction "2_2") (pintype "passive"))
    )
    (net (code "16") (name "/IN2") (class "Default")
      (node (ref "J5") (pin "2") (pinfunction "2_2") (pintype "passive"))
      (node (ref "R30") (pin "2") (pinfunction "2_2") (pintype "passive"))
    )
    (net (code "17") (name "/IN3") (class "Default")
      (node (ref "J5") (pin "3") (pinfunction "3_3") (pintype "passive"))
      (node (ref "R31") (pin "2") (pinfunction "2_2") (pintype "passive"))
    )
    (net (code "18") (name "/IN4") (class "Default")
      (node (ref "J5") (pin "4") (pinfunction "4_4") (pintype "passive"))
      (node (ref "R32") (pin "2") (pinfunction "2_2") (pintype "passive"))
    )
    (net (code "19") (name "/IN5") (class "Default")
      (node (ref "J5") (pin "5") (pinfunction "5_5") (pintype "passive"))
      (node (ref "R33") (pin "2") (pinfunction "2_2") (pintype "passive"))
    )
    (net (code "20") (name "/IN6") (class "Default")
      (node (ref "J5") (pin "6") (pinfunction "6_6") (pintype "passive"))
      (node (ref "R34") (pin "2") (pinfunction "2_2") (pintype "passive"))
    )
    (net (code "21") (name "/IN7") (class "Default")
      (node (ref "J5") (pin "7") (pinfunction "7_7") (pintype "passive"))
      (node (ref "R35") (pin "2") (pinfunction "2_2") (pintype "passive"))
    )
    (net (code "22") (name "/IN8") (class "Default")
      (node (ref "J5") (pin "8") (pinfunction "8_8") (pintype "passive"))
      (node (ref "R36") (pin "2") (pinfunction "2_2") (pintype "passive"))
    )
    (net (code "23") (name "/MISO") (class "Default")
      (node (ref "J9") (pin "11") (pinfunction "11_11") (pintype "passive"))
      (node (ref "U4") (pin "21") (pinfunction "MISO_21") (pintype "passive"))
    )
    (net (code "24") (name "/MOSI") (class "Default")
      (node (ref "J9") (pin "12") (pinfunction "12_12") (pintype "passive"))
      (node (ref "U4") (pin "19") (pinfunction "MOSI_19") (pintype "passive"))
    )
    (net (code "25") (name "/NC1") (class "Default")
      (node (ref "J1") (pin "1") (pinfunction "1_1") (pintype "passive"))
      (node (ref "K1") (pin "NC") (pinfunction "NC_NC") (pintype "passive"))
    )
    (net (code "26") (name "/NC2") (class "Default")
      (node (ref "J2") (pin "1") (pinfunction "1_1") (pintype "passive"))
      (node (ref "K2") (pin "NC") (pinfunction "NC_NC") (pintype "passive"))
    )
    (net (code "27") (name "/NC3") (class "Default")
      (node (ref "J3") (pin "1") (pinfunction "1_1") (pintype "passive"))
      (node (ref "K3") (pin "NC") (pinfunction "NC_NC") (pintype "passive"))
    )
    (net (code "28") (name "/NC4") (class "Default")
      (node (ref "J4") (pin "1") (pinfunction "1_1") (pintype "passive"))
      (node (ref "K4") (pin "NC") (pinfunction "NC_NC") (pintype "passive"))
    )
    (net (code "29") (name "/NO1") (class "Default")
      (node (ref "J1") (pin "3") (pinfunction "3_3") (pintype "passive"))
      (node (ref "K1") (pin "NO") (pinfunction "NO_NO") (pintype "passive"))
    )
    (net (code "30") (name "/NO2") (class "Default")
      (node (ref "J2") (pin "3") (pinfunction "3_3") (pintype "passive"))
      (node (ref "K2") (pin "NO") (pinfunction "NO_NO") (pintype "passive"))
    )
    (net (code "31") (name "/NO3") (class "Default")
      (node (ref "J3") (pin "3") (pinfunction "3_3") (pintype "passive"))
      (node (ref "K3") (pin "NO") (pinfunction "NO_NO") (pintype "passive"))
    )
    (net (code "32") (name "/NO4") (class "Default")
      (node (ref "J4") (pin "3") (pinfunction "3_3") (pintype "passive"))
      (node (ref "K4") (pin "NO") (pinfunction "NO_NO") (pintype "passive"))
    )
    (net (code "33") (name "/OI1") (class "Default")
      (node (ref "D13") (pin "3") (pinfunction "3_3") (pintype "passive"))
      (node (ref "R17") (pin "2") (pinfunction "2_2") (pintype "passive"))
      (node (ref "U4") (pin "7") (pinfunction "GPIO4_7") (pintype "passive"))
    )
    (net (code "34") (name "/OI2") (class "Default")
      (node (ref "D14") (pin "3") (pinfunction "3_3") (pintype "passive"))
      (node (ref "R18") (pin "2") (pinfunction "2_2") (pintype "passive"))
      (node (ref "U4") (pin "11") (pinfunction "GPIO17_11") (pintype "passive"))
    )
    (net (code "35") (name "/OI3") (class "Default")
      (node (ref "D15") (pin "3") (pinfunction "3_3") (pintype "passive"))
      (node (ref "R19") (pin "2") (pinfunction "2_2") (pintype "passive"))
      (node (ref "U4") (pin "13") (pinfunction "GPIO27_13") (pintype "passive"))
    )
    (net (code "36") (name "/OI4") (class "Default")
      (node (ref "D16") (pin "3") (pinfunction "3_3") (pintype "passive"))
      (node (ref "R20") (pin "2") (pinfunction "2_2") (pintype "passive"))
      (node (ref "U4") (pin "15") (pinfunction "GPIO22_15") (pintype "passive"))
    )
    (net (code "37") (name "/OI5") (class "Default")
      (node (ref "D17") (pin "3") (pinfunction "3_3") (pintype "passive"))
      (node (ref "R21") (pin "2") (pinfunction "2_2") (pintype "passive"))
      (node (ref "U4") (pin "29") (pinfunction "GPIO5_29") (pintype "passive"))
    )
    (net (code "38") (name "/OI6") (class "Default")
      (node (ref "D18") (pin "3") (pinfunction "3_3") (pintype "passive"))
      (node (ref "R22") (pin "2") (pinfunction "2_2") (pintype "passive"))
      (node (ref "U4") (pin "31") (pinfunction "GPIO6_31") (pintype "passive"))
    )
    (net (code "39") (name "/OI7") (class "Default")
      (node (ref "D19") (pin "3") (pinfunction "3_3") (pintype "passive"))
      (node (ref "R23") (pin "2") (pinfunction "2_2") (pintype "passive"))
      (node (ref "U4") (pin "36") (pinfunction "GPIO16_36") (pintype "passive"))
    )
    (net (code "40") (name "/OI8") (class "Default")
      (node (ref "D20") (pin "3") (pinfunction "3_3") (pintype "passive"))
      (node (ref "R24") (pin "2") (pinfunction "2_2") (pintype "passive"))
      (node (ref "U4") (pin "38") (pinfunction "GPIO20_38") (pintype "passive"))
    )
    (net (code "41") (name "/RXD") (class "Default")
      (node (ref "J9") (pin "20") (pinfunction "20_20") (pintype "passive"))
      (node (ref "U4") (pin "10") (pinfunction "RXD_10") (pintype "passive"))
    )
    (net (code "42") (name "/Rele1") (class "Default")
      (node (ref "R16") (pin "1") (pinfunction "1_1") (pintype "passive"))
      (node (ref "U4") (pin "37") (pinfunction "GPIO26_37") (pintype "passive"))
    )
    (net (code "43") (name "/Rele2") (class "Default")
      (node (ref "R15") (pin "1") (pinfunction "1_1") (pintype "passive"))
      (node (ref "U4") (pin "22") (pinfunction "GPIO25_22") (pintype "passive"))
    )
    (net (code "44") (name "/Rele3") (class "Default")
      (node (ref "R14") (pin "1") (pinfunction "1_1") (pintype "passive"))
      (node (ref "U4") (pin "18") (pinfunction "GPIO24_18") (pintype "passive"))
    )
    (net (code "45") (name "/Rele4") (class "Default")
      (node (ref "R13") (pin "1") (pinfunction "1_1") (pintype "passive"))
      (node (ref "U4") (pin "16") (pinfunction "GPIO23_16") (pintype "passive"))
    )
    (net (code "46") (name "/SCL") (class "Default")
      (node (ref "J9") (pin "10") (pinfunction "10_10") (pintype "passive"))
      (node (ref "U4") (pin "5") (pinfunction "SCL_5") (pintype "passive"))
    )
    (net (code "47") (name "/SCLK") (class "Default")
      (node (ref "J9") (pin "13") (pinfunction "13_13") (pintype "passive"))
      (node (ref "U4") (pin "23") (pinfunction "SCLK_23") (pintype "passive"))
    )
    (net (code "48") (name "/SDA") (class "Default")
      (node (ref "J9") (pin "9") (pinfunction "9_9") (pintype "passive"))
      (node (ref "U4") (pin "3") (pinfunction "SDA_3") (pintype "passive"))
    )
    (net (code "49") (name "/TXD") (class "Default")
      (node (ref "J9") (pin "19") (pinfunction "19_19") (pintype "passive"))
      (node (ref "U4") (pin "8") (pinfunction "TXD_8") (pintype "passive"))
    )
    (net (code "50") (name "3V3") (class "Default")
      (node (ref "D13") (pin "4") (pinfunction "4_4") (pintype "passive"))
      (node (ref "D14") (pin "4") (pinfunction "4_4") (pintype "passive"))
      (node (ref "D15") (pin "4") (pinfunction "4_4") (pintype "passive"))
      (node (ref "D16") (pin "4") (pinfunction "4_4") (pintype "passive"))
      (node (ref "D17") (pin "4") (pinfunction "4_4") (pintype "passive"))
      (node (ref "D18") (pin "4") (pinfunction "4_4") (pintype "passive"))
      (node (ref "D19") (pin "4") (pinfunction "4_4") (pintype "passive"))
      (node (ref "D20") (pin "4") (pinfunction "4_4") (pintype "passive"))
      (node (ref "J9") (pin "7") (pinfunction "7_7") (pintype "passive"))
      (node (ref "U4") (pin "1") (pinfunction "3.3V_1") (pintype "passive"))
      (node (ref "U4") (pin "17") (pinfunction "3.3V_17") (pintype "passive"))
    )
    (net (code "51") (name "GND") (class "Default")
      (node (ref "C4") (pin "1") (pinfunction "C_1") (pintype "passive"))
      (node (ref "C5") (pin "1") (pinfunction "C_1") (pintype "passive"))
      (node (ref "D13") (pin "2") (pinfunction "2_2") (pintype "passive"))
      (node (ref "D14") (pin "2") (pinfunction "2_2") (pintype "passive"))
      (node (ref "D15") (pin "2") (pinfunction "2_2") (pintype "passive"))
      (node (ref "D16") (pin "2") (pinfunction "2_2") (pintype "passive"))
      (node (ref "D17") (pin "2") (pinfunction "2_2") (pintype "passive"))
      (node (ref "D18") (pin "2") (pinfunction "2_2") (pintype "passive"))
      (node (ref "D19") (pin "2") (pinfunction "2_2") (pintype "passive"))
      (node (ref "D20") (pin "2") (pinfunction "2_2") (pintype "passive"))
      (node (ref "J8") (pin "1") (pinfunction "1_1") (pintype "passive"))
      (node (ref "J8") (pin "2") (pinfunction "2_2") (pintype "passive"))
      (node (ref "J8") (pin "3") (pinfunction "3_3") (pintype "passive"))
      (node (ref "J9") (pin "16") (pinfunction "16_16") (pintype "passive"))
      (node (ref "J9") (pin "18") (pinfunction "18_18") (pintype "passive"))
      (node (ref "J9") (pin "6") (pinfunction "6_6") (pintype "passive"))
      (node (ref "J9") (pin "8") (pinfunction "8_8") (pintype "passive"))
      (node (ref "Q1") (pin "2") (pinfunction "E_2") (pintype "passive"))
      (node (ref "Q2") (pin "2") (pinfunction "E_2") (pintype "passive"))
      (node (ref "Q3") (pin "2") (pinfunction "E_2") (pintype "passive"))
      (node (ref "Q4") (pin "2") (pinfunction "E_2") (pintype "passive"))
      (node (ref "Q5") (pin "2") (pinfunction "E_2") (pintype "passive"))
      (node (ref "Q6") (pin "2") (pinfunction "E_2") (pintype "passive"))
      (node (ref "Q7") (pin "2") (pinfunction "E_2") (pintype "passive"))
      (node (ref "Q8") (pin "2") (pinfunction "E_2") (pintype "passive"))
      (node (ref "R17") (pin "1") (pinfunction "1_1") (pintype "passive"))
      (node (ref "R18") (pin "1") (pinfunction "1_1") (pintype "passive"))
      (node (ref "R19") (pin "1") (pinfunction "1_1") (pintype "passive"))
      (node (ref "R20") (pin "1") (pinfunction "1_1") (pintype "passive"))
      (node (ref "R21") (pin "1") (pinfunction "1_1") (pintype "passive"))
      (node (ref "R22") (pin "1") (pinfunction "1_1") (pintype "passive"))
      (node (ref "R23") (pin "1") (pinfunction "1_1") (pintype "passive"))
      (node (ref "R24") (pin "1") (pinfunction "1_1") (pintype "passive"))
      (node (ref "R25") (pin "1") (pinfunction "1_1") (pintype "passive"))
      (node (ref "R26") (pin "1") (pinfunction "1_1") (pintype "passive"))
      (node (ref "R27") (pin "1") (pinfunction "1_1") (pintype "passive"))
      (node (ref "R28") (pin "1") (pinfunction "1_1") (pintype "passive"))
      (node (ref "U2") (pin "16") (pinfunction "-V_OUTPUT_16") (pintype "passive"))
      (node (ref "U2") (pin "2") (pinfunction "-V_INPUT_2") (pintype "passive"))
      (node (ref "U2") (pin "3") (pinfunction "-V_INPUT_3") (pintype "passive"))
      (node (ref "U2") (pin "9") (pinfunction "-V_OUTPUT_9") (pintype "passive"))
      (node (ref "U3") (pin "1") (pinfunction "GND_1") (pintype "power_in"))
      (node (ref "U4") (pin "14") (pinfunction "GND_14") (pintype "passive"))
      (node (ref "U4") (pin "20") (pinfunction "GND_20") (pintype "passive"))
      (node (ref "U4") (pin "25") (pinfunction "GND_25") (pintype "passive"))
      (node (ref "U4") (pin "30") (pinfunction "GND_30") (pintype "passive"))
      (node (ref "U4") (pin "34") (pinfunction "GND_34") (pintype "passive"))
      (node (ref "U4") (pin "39") (pinfunction "GND_39") (pintype "passive"))
      (node (ref "U4") (pin "6") (pinfunction "GND_6") (pintype "passive"))
      (node (ref "U4") (pin "9") (pinfunction "GND_9") (pintype "passive"))
    )
    (net (code "52") (name "Net-(D1-Pad2)") (class "Default")
      (node (ref "D1") (pin "2") (pinfunction "2_2") (pintype "passive"))
      (node (ref "R1") (pin "1") (pinfunction "1_1") (pintype "passive"))
    )
    (net (code "53") (name "Net-(D1-Pad3)") (class "Default")
      (node (ref "D1") (pin "3") (pinfunction "3_3") (pintype "passive"))
      (node (ref "R9") (pin "1") (pinfunction "1_1") (pintype "passive"))
    )
    (net (code "54") (name "Net-(D2-Pad2)") (class "Default")
      (node (ref "D2") (pin "2") (pinfunction "2_2") (pintype "passive"))
      (node (ref "R2") (pin "1") (pinfunction "1_1") (pintype "passive"))
    )
    (net (code "55") (name "Net-(D2-Pad3)") (class "Default")
      (node (ref "D2") (pin "3") (pinfunction "3_3") (pintype "passive"))
      (node (ref "R10") (pin "1") (pinfunction "1_1") (pintype "passive"))
    )
    (net (code "56") (name "Net-(D3-Pad2)") (class "Default")
      (node (ref "D3") (pin "2") (pinfunction "2_2") (pintype "passive"))
      (node (ref "R3") (pin "1") (pinfunction "1_1") (pintype "passive"))
    )
    (net (code "57") (name "Net-(D3-Pad3)") (class "Default")
      (node (ref "D3") (pin "3") (pinfunction "3_3") (pintype "passive"))
      (node (ref "R11") (pin "1") (pinfunction "1_1") (pintype "passive"))
    )
    (net (code "58") (name "Net-(D4-Pad2)") (class "Default")
      (node (ref "D4") (pin "2") (pinfunction "2_2") (pintype "passive"))
      (node (ref "R4") (pin "1") (pinfunction "1_1") (pintype "passive"))
    )
    (net (code "59") (name "Net-(D4-Pad3)") (class "Default")
      (node (ref "D4") (pin "3") (pinfunction "3_3") (pintype "passive"))
      (node (ref "R12") (pin "1") (pinfunction "1_1") (pintype "passive"))
    )
    (net (code "60") (name "Net-(D5-Pad2)") (class "Default")
      (node (ref "D5") (pin "2") (pinfunction "2_2") (pintype "passive"))
      (node (ref "R5") (pin "2") (pinfunction "2_2") (pintype "passive"))
    )
    (net (code "61") (name "Net-(D6-Pad2)") (class "Default")
      (node (ref "D6") (pin "2") (pinfunction "2_2") (pintype "passive"))
      (node (ref "R6") (pin "2") (pinfunction "2_2") (pintype "passive"))
    )
    (net (code "62") (name "Net-(D7-Pad2)") (class "Default")
      (node (ref "D7") (pin "2") (pinfunction "2_2") (pintype "passive"))
      (node (ref "R7") (pin "2") (pinfunction "2_2") (pintype "passive"))
    )
    (net (code "63") (name "Net-(D8-Pad2)") (class "Default")
      (node (ref "D8") (pin "2") (pinfunction "2_2") (pintype "passive"))
      (node (ref "R8") (pin "2") (pinfunction "2_2") (pintype "passive"))
    )
    (net (code "64") (name "Net-(D13-Pad1)") (class "Default")
      (node (ref "D13") (pin "1") (pinfunction "1_1") (pintype "passive"))
      (node (ref "R29") (pin "1") (pinfunction "1_1") (pintype "passive"))
    )
    (net (code "65") (name "Net-(D14-Pad1)") (class "Default")
      (node (ref "D14") (pin "1") (pinfunction "1_1") (pintype "passive"))
      (node (ref "R30") (pin "1") (pinfunction "1_1") (pintype "passive"))
    )
    (net (code "66") (name "Net-(D15-Pad1)") (class "Default")
      (node (ref "D15") (pin "1") (pinfunction "1_1") (pintype "passive"))
      (node (ref "R31") (pin "1") (pinfunction "1_1") (pintype "passive"))
    )
    (net (code "67") (name "Net-(D16-Pad1)") (class "Default")
      (node (ref "D16") (pin "1") (pinfunction "1_1") (pintype "passive"))
      (node (ref "R32") (pin "1") (pinfunction "1_1") (pintype "passive"))
    )
    (net (code "68") (name "Net-(D17-Pad1)") (class "Default")
      (node (ref "D17") (pin "1") (pinfunction "1_1") (pintype "passive"))
      (node (ref "R33") (pin "1") (pinfunction "1_1") (pintype "passive"))
    )
    (net (code "69") (name "Net-(D18-Pad1)") (class "Default")
      (node (ref "D18") (pin "1") (pinfunction "1_1") (pintype "passive"))
      (node (ref "R34") (pin "1") (pinfunction "1_1") (pintype "passive"))
    )
    (net (code "70") (name "Net-(D19-Pad1)") (class "Default")
      (node (ref "D19") (pin "1") (pinfunction "1_1") (pintype "passive"))
      (node (ref "R35") (pin "1") (pinfunction "1_1") (pintype "passive"))
    )
    (net (code "71") (name "Net-(D20-Pad1)") (class "Default")
      (node (ref "D20") (pin "1") (pinfunction "1_1") (pintype "passive"))
      (node (ref "R36") (pin "1") (pinfunction "1_1") (pintype "passive"))
    )
    (net (code "72") (name "Net-(Q1-B)") (class "Default")
      (node (ref "Q1") (pin "1") (pinfunction "B_1") (pintype "passive"))
      (node (ref "R13") (pin "2") (pinfunction "2_2") (pintype "passive"))
      (node (ref "R25") (pin "2") (pinfunction "2_2") (pintype "passive"))
    )
    (net (code "73") (name "Net-(Q1-C)") (class "Default")
      (node (ref "Q1") (pin "3") (pinfunction "C_3") (pintype "passive"))
      (node (ref "R1") (pin "2") (pinfunction "2_2") (pintype "passive"))
    )
    (net (code "74") (name "Net-(Q2-B)") (class "Default")
      (node (ref "Q2") (pin "1") (pinfunction "B_1") (pintype "passive"))
      (node (ref "R14") (pin "2") (pinfunction "2_2") (pintype "passive"))
      (node (ref "R26") (pin "2") (pinfunction "2_2") (pintype "passive"))
    )
    (net (code "75") (name "Net-(Q2-C)") (class "Default")
      (node (ref "Q2") (pin "3") (pinfunction "C_3") (pintype "passive"))
      (node (ref "R2") (pin "2") (pinfunction "2_2") (pintype "passive"))
    )
    (net (code "76") (name "Net-(Q3-B)") (class "Default")
      (node (ref "Q3") (pin "1") (pinfunction "B_1") (pintype "passive"))
      (node (ref "R15") (pin "2") (pinfunction "2_2") (pintype "passive"))
      (node (ref "R27") (pin "2") (pinfunction "2_2") (pintype "passive"))
    )
    (net (code "77") (name "Net-(Q3-C)") (class "Default")
      (node (ref "Q3") (pin "3") (pinfunction "C_3") (pintype "passive"))
      (node (ref "R3") (pin "2") (pinfunction "2_2") (pintype "passive"))
    )
    (net (code "78") (name "Net-(Q4-B)") (class "Default")
      (node (ref "Q4") (pin "1") (pinfunction "B_1") (pintype "passive"))
      (node (ref "R16") (pin "2") (pinfunction "2_2") (pintype "passive"))
      (node (ref "R28") (pin "2") (pinfunction "2_2") (pintype "passive"))
    )
    (net (code "79") (name "Net-(Q4-C)") (class "Default")
      (node (ref "Q4") (pin "3") (pinfunction "C_3") (pintype "passive"))
      (node (ref "R4") (pin "2") (pinfunction "2_2") (pintype "passive"))
    )
    (net (code "80") (name "Net-(Q5-B)") (class "Default")
      (node (ref "Q5") (pin "1") (pinfunction "B_1") (pintype "passive"))
      (node (ref "R9") (pin "2") (pinfunction "2_2") (pintype "passive"))
    )
    (net (code "81") (name "Net-(Q5-C)") (class "Default")
      (node (ref "D9") (pin "1") (pinfunction "1_1") (pintype "passive"))
      (node (ref "K1") (pin "A2") (pinfunction "A2_A2") (pintype "passive"))
      (node (ref "Q5") (pin "3") (pinfunction "C_3") (pintype "passive"))
      (node (ref "R5") (pin "1") (pinfunction "1_1") (pintype "passive"))
    )
    (net (code "82") (name "Net-(Q6-B)") (class "Default")
      (node (ref "Q6") (pin "1") (pinfunction "B_1") (pintype "passive"))
      (node (ref "R10") (pin "2") (pinfunction "2_2") (pintype "passive"))
    )
    (net (code "83") (name "Net-(Q6-C)") (class "Default")
      (node (ref "D10") (pin "1") (pinfunction "1_1") (pintype "passive"))
      (node (ref "K2") (pin "A2") (pinfunction "A2_A2") (pintype "passive"))
      (node (ref "Q6") (pin "3") (pinfunction "C_3") (pintype "passive"))
      (node (ref "R6") (pin "1") (pinfunction "1_1") (pintype "passive"))
    )
    (net (code "84") (name "Net-(Q7-B)") (class "Default")
      (node (ref "Q7") (pin "1") (pinfunction "B_1") (pintype "passive"))
      (node (ref "R11") (pin "2") (pinfunction "2_2") (pintype "passive"))
    )
    (net (code "85") (name "Net-(Q7-C)") (class "Default")
      (node (ref "D11") (pin "1") (pinfunction "1_1") (pintype "passive"))
      (node (ref "K3") (pin "A2") (pinfunction "A2_A2") (pintype "passive"))
      (node (ref "Q7") (pin "3") (pinfunction "C_3") (pintype "passive"))
      (node (ref "R7") (pin "1") (pinfunction "1_1") (pintype "passive"))
    )
    (net (code "86") (name "Net-(Q8-B)") (class "Default")
      (node (ref "Q8") (pin "1") (pinfunction "B_1") (pintype "passive"))
      (node (ref "R12") (pin "2") (pinfunction "2_2") (pintype "passive"))
    )
    (net (code "87") (name "Net-(Q8-C)") (class "Default")
      (node (ref "D12") (pin "1") (pinfunction "1_1") (pintype "passive"))
      (node (ref "K4") (pin "A2") (pinfunction "A2_A2") (pintype "passive"))
      (node (ref "Q8") (pin "3") (pinfunction "C_3") (pintype "passive"))
      (node (ref "R8") (pin "1") (pinfunction "1_1") (pintype "passive"))
    )
    (net (code "88") (name "unconnected-(U2-NO_CONECT-Pad10)") (class "Default")
      (node (ref "U2") (pin "10") (pinfunction "NO_CONECT_10") (pintype "passive"))
    )
    (net (code "89") (name "unconnected-(U2-NO_CONECT-Pad15)") (class "Default")
      (node (ref "U2") (pin "15") (pinfunction "NO_CONECT_15") (pintype "passive"))
    )
    (net (code "90") (name "unconnected-(U2-NO_PIN-Pad1)") (class "Default")
      (node (ref "U2") (pin "1") (pinfunction "NO_PIN_1") (pintype "passive"))
    )
    (net (code "91") (name "unconnected-(U2-NO_PIN-Pad12)") (class "Default")
      (node (ref "U2") (pin "12") (pinfunction "NO_PIN_12") (pintype "passive"))
    )
    (net (code "92") (name "unconnected-(U2-NO_PIN-Pad13)") (class "Default")
      (node (ref "U2") (pin "13") (pinfunction "NO_PIN_13") (pintype "passive"))
    )
    (net (code "93") (name "unconnected-(U2-NO_PIN-Pad24)") (class "Default")
      (node (ref "U2") (pin "24") (pinfunction "NO_PIN_24") (pintype "passive"))
    )
    (net (code "94") (name "unconnected-(U4-DNC-Pad27)") (class "Default")
      (node (ref "U4") (pin "27") (pinfunction "DNC_27") (pintype "passive"))
    )
    (net (code "95") (name "unconnected-(U4-DNC-Pad28)") (class "Default")
      (node (ref "U4") (pin "28") (pinfunction "DNC_28") (pintype "passive"))
    )
  )
)
